# KW2CPU_PCB.net
KiCad netlist of a schematic drawn in EAGLE
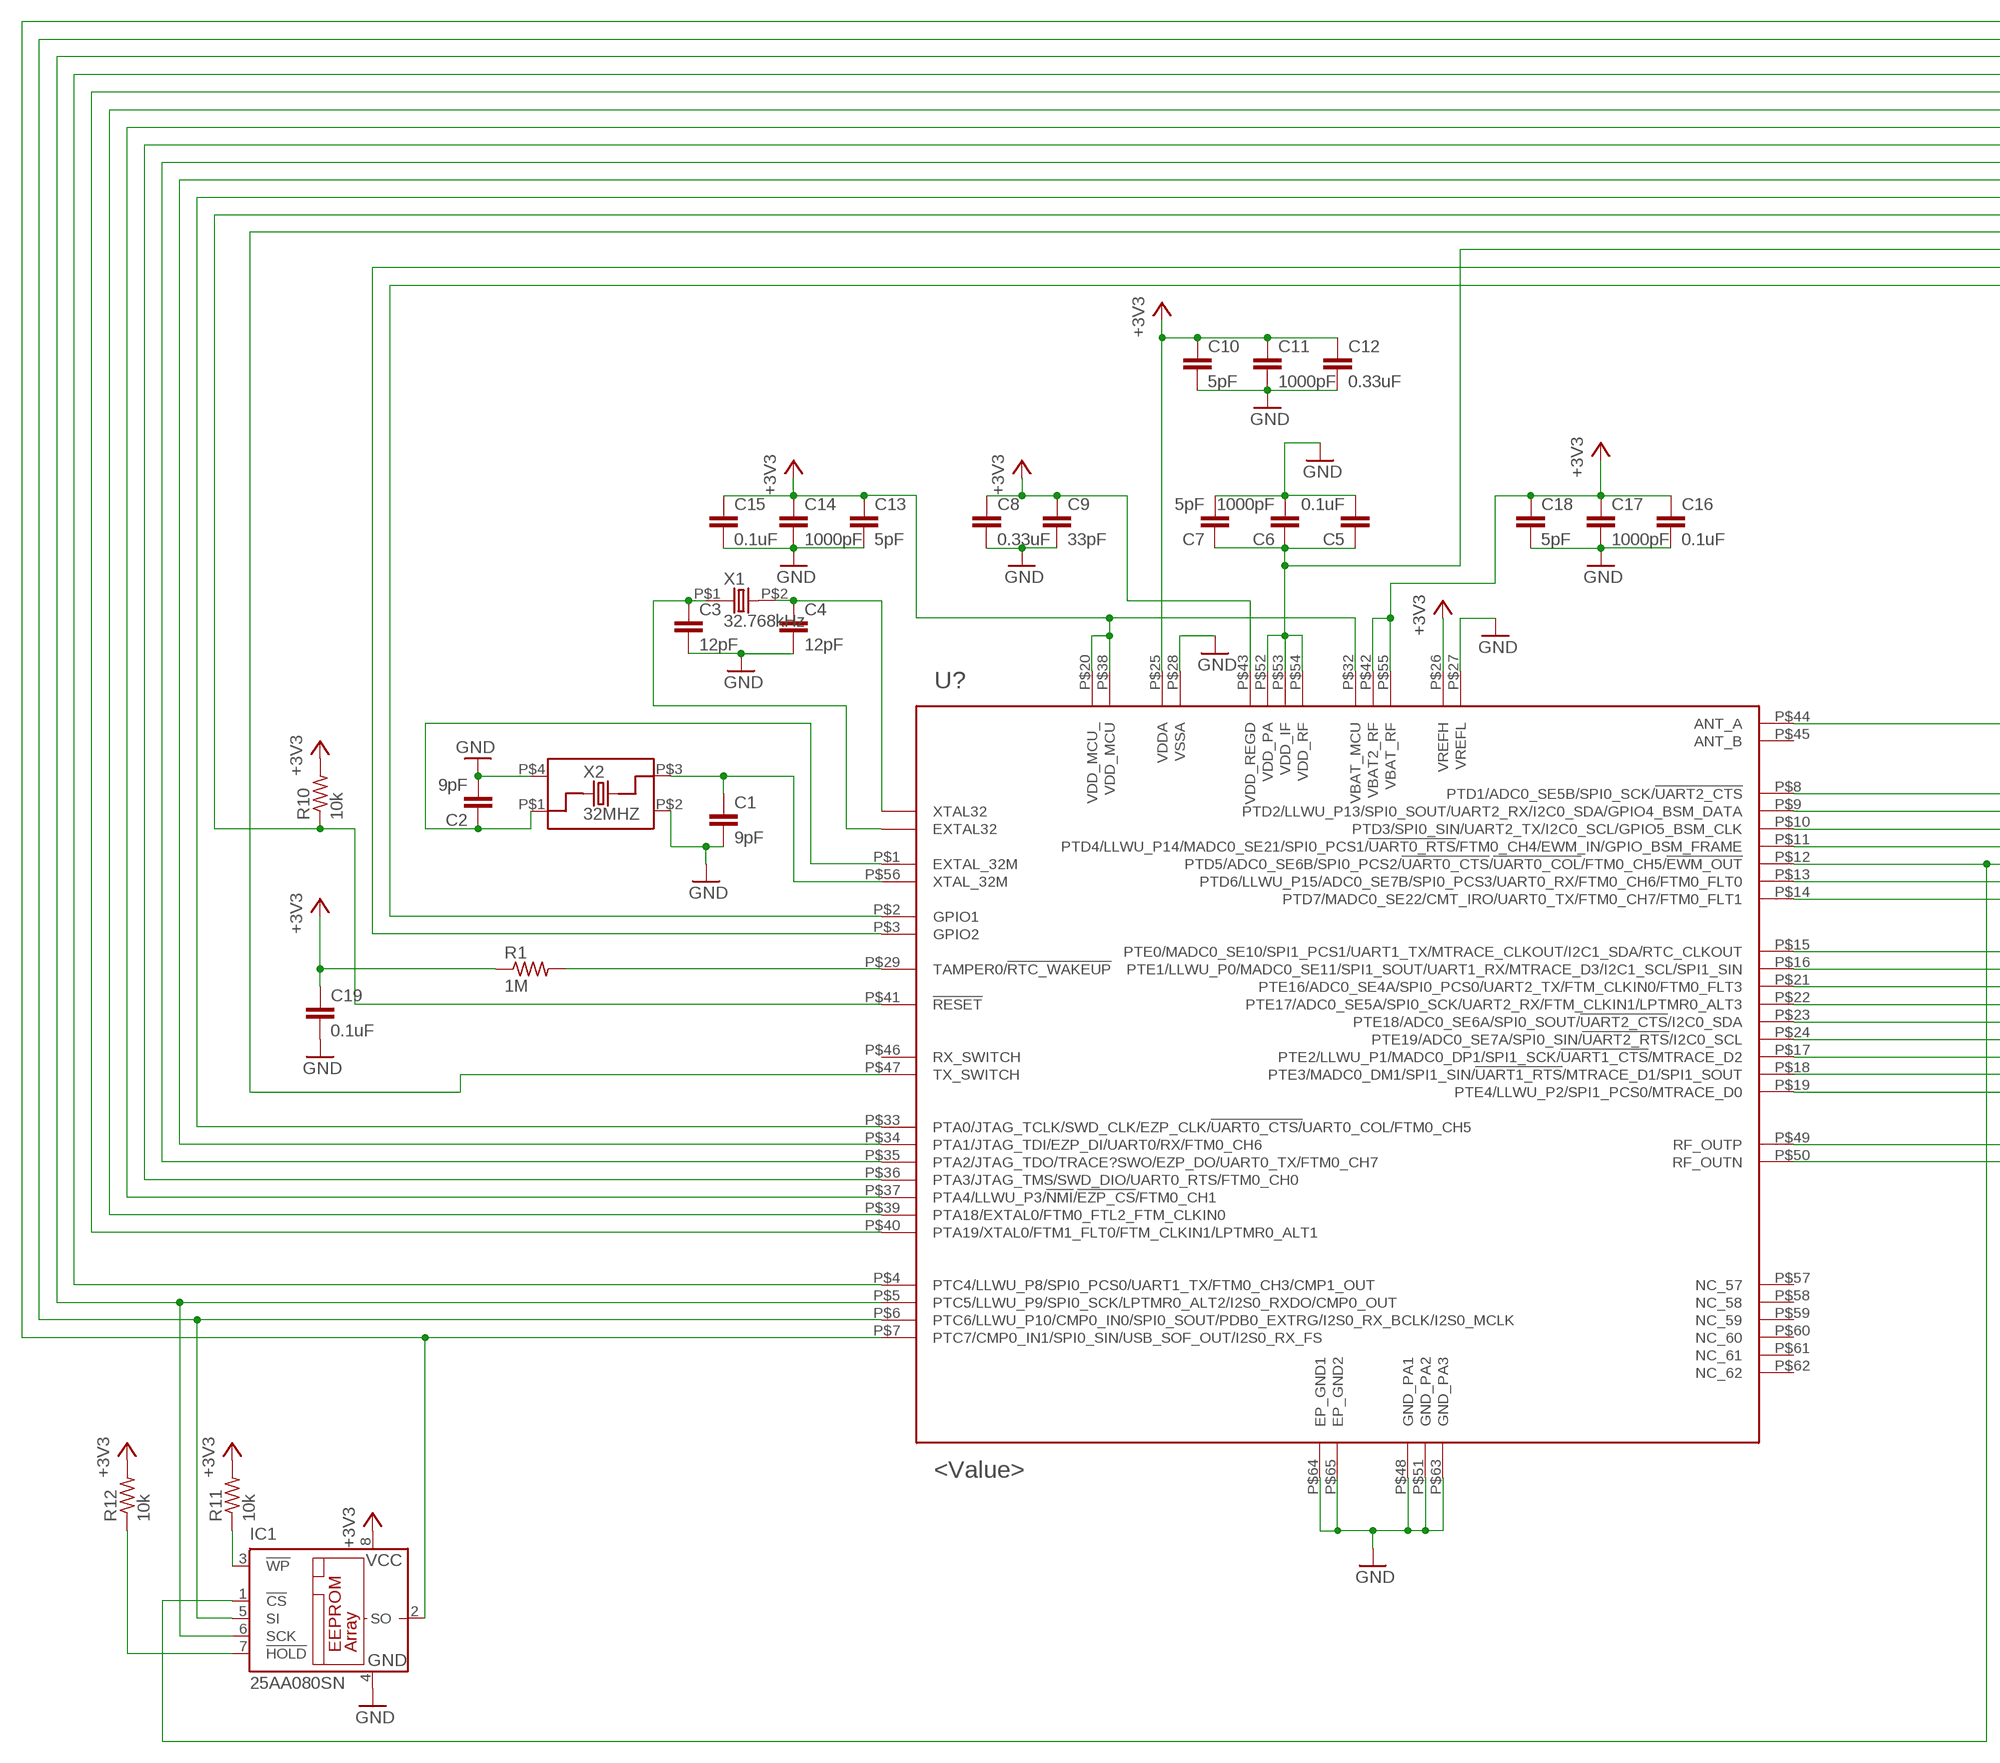
[diagram p0: schematic, sheet 1, part 1 of 2]
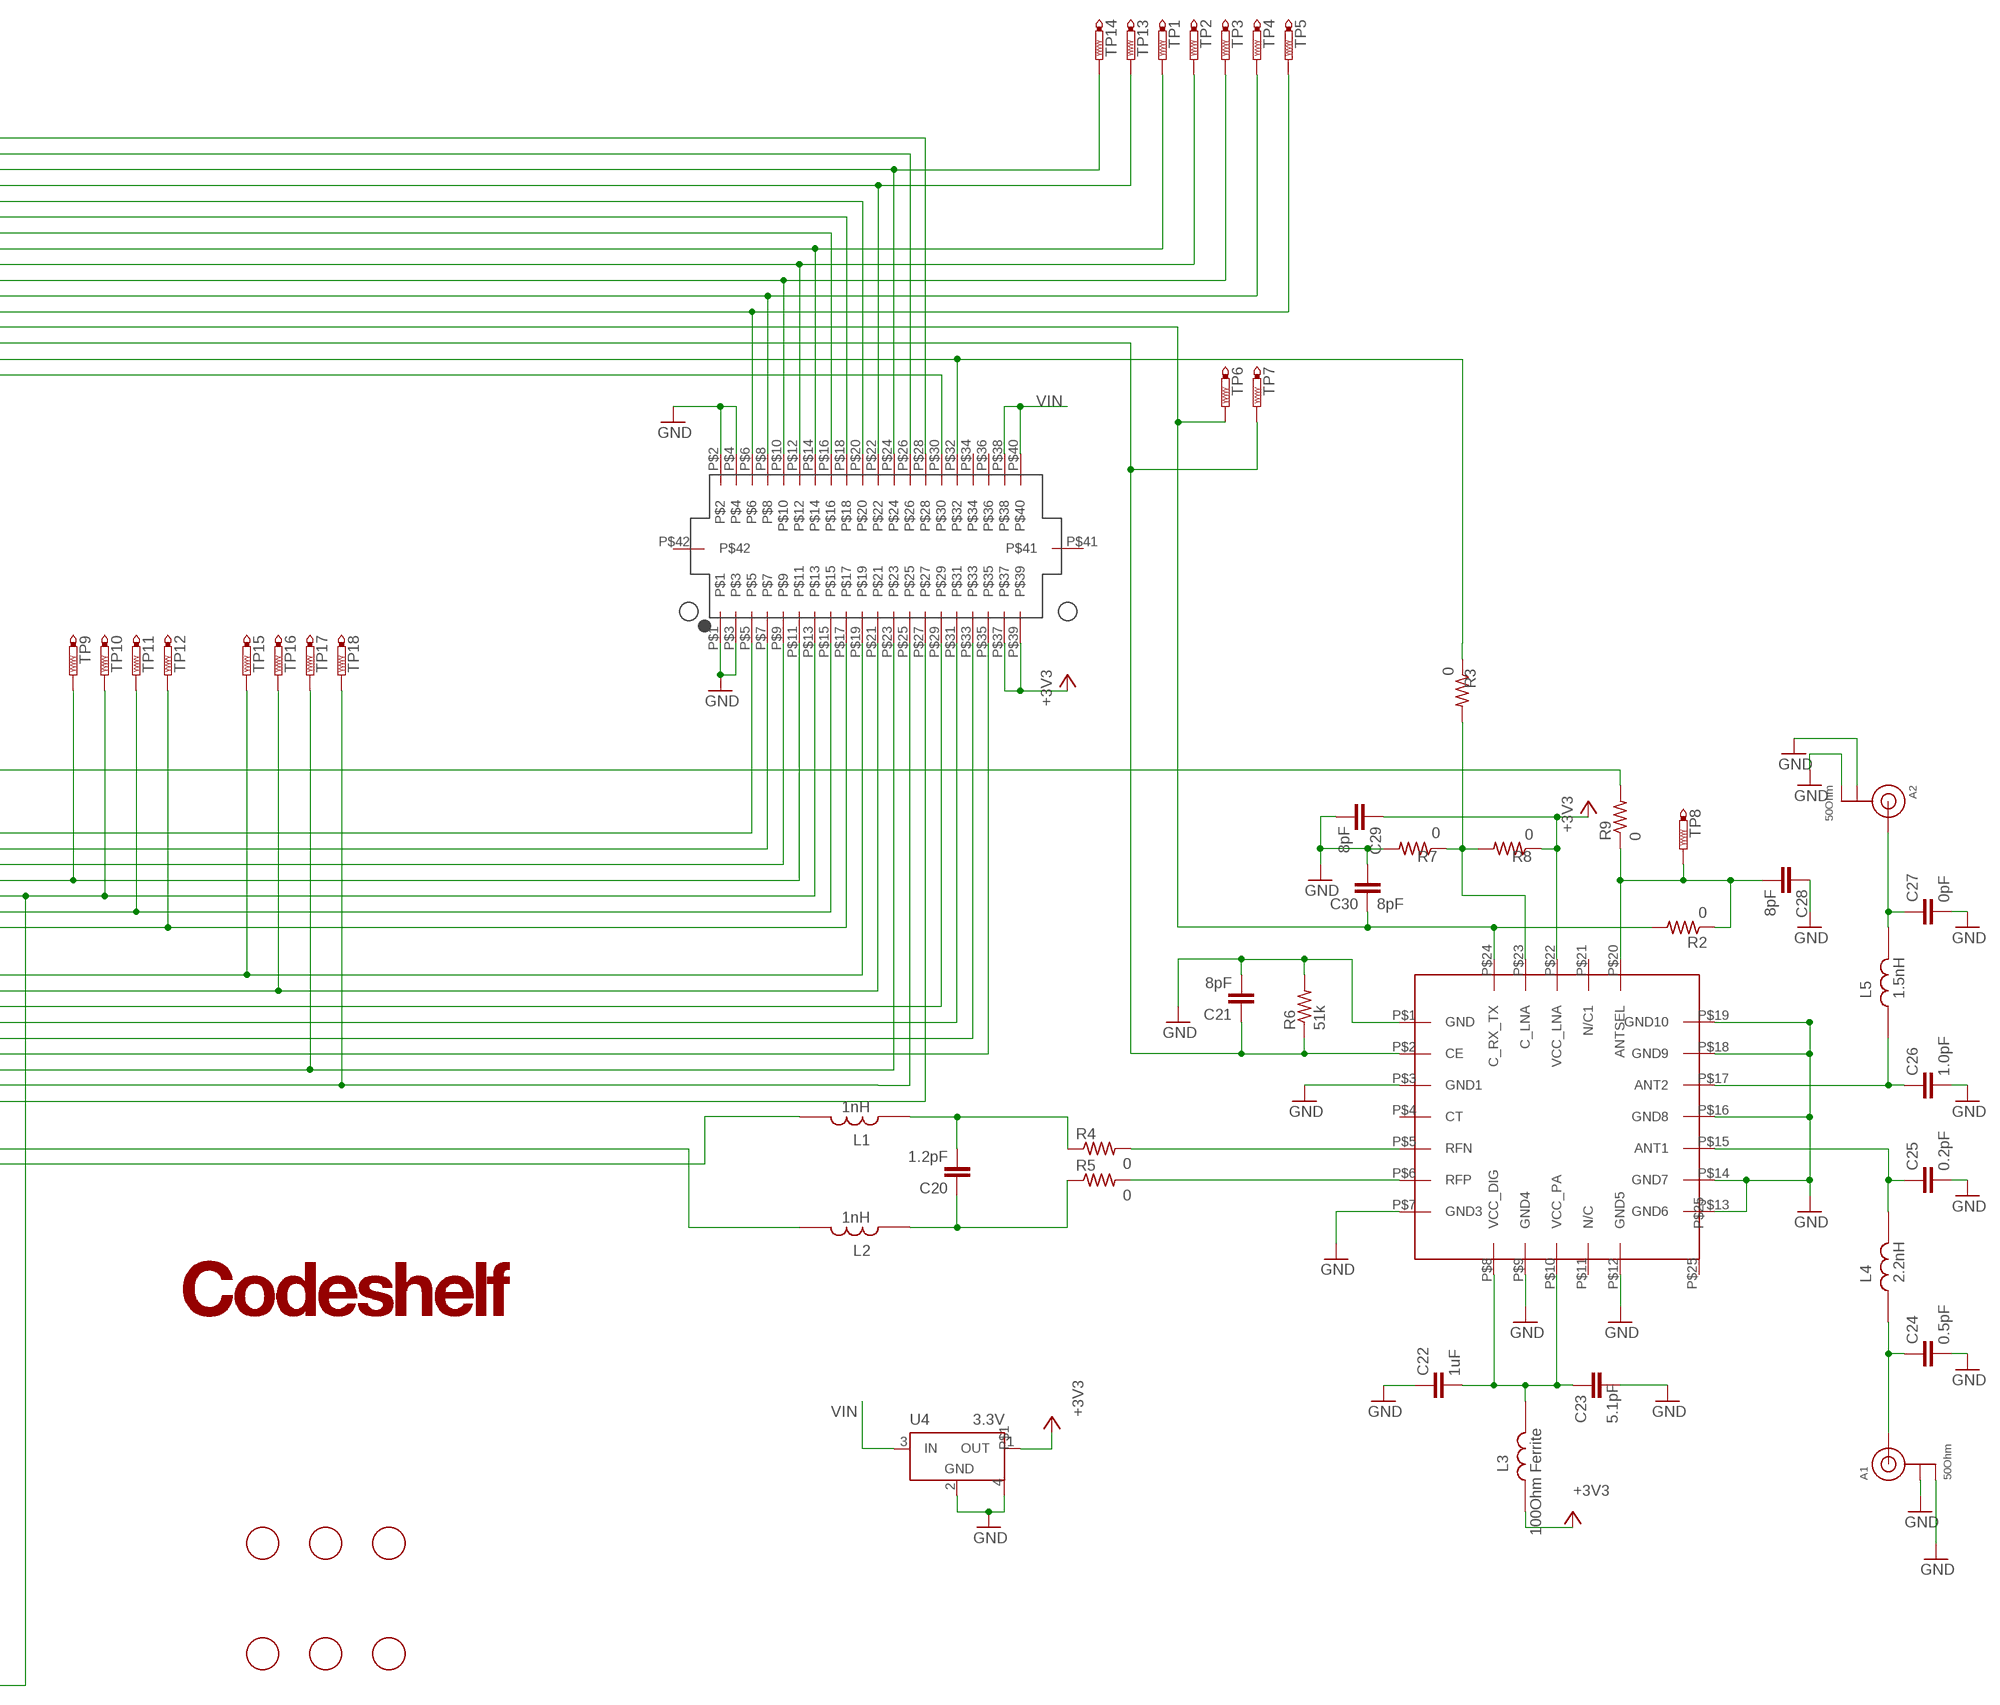
[diagram p1: schematic, sheet 1, part 2 of 2]

(export (version "E")
  (design (tool "Eeschema 10.0.6"))
  (components
    (comp (ref "A1")
      (value "50Ohm")
      (footprint "eagle-import:U.FL")
      (libsource (lib "eagle-import") (part "ANTENNA_U.FL"))
    )
    (comp (ref "A2")
      (value "50Ohm")
      (footprint "eagle-import:U.FL")
      (fields (field (name "MFGN") "Hirose") (field (name "MFGP") "N.FL-R-SMT-1(10)"))
      (libsource (lib "eagle-import") (part "ANTENNA_U.FL"))
    )
    (comp (ref "C1")
      (value "9pF")
      (footprint "eagle-import:C0402")
      (libsource (lib "eagle-import") (part "RF-C0402"))
    )
    (comp (ref "C2")
      (value "9pF")
      (footprint "eagle-import:C0402")
      (libsource (lib "eagle-import") (part "RF-C0402"))
    )
    (comp (ref "C3")
      (value "12pF")
      (footprint "eagle-import:C0402")
      (libsource (lib "eagle-import") (part "RF-C0402"))
    )
    (comp (ref "C4")
      (value "12pF")
      (footprint "eagle-import:C0402")
      (libsource (lib "eagle-import") (part "RF-C0402"))
    )
    (comp (ref "C5")
      (value "0.1uF")
      (footprint "eagle-import:C0402")
      (libsource (lib "eagle-import") (part "RF-C0402"))
    )
    (comp (ref "C6")
      (value "1000pF")
      (footprint "eagle-import:C0402")
      (libsource (lib "eagle-import") (part "RF-C0402"))
    )
    (comp (ref "C7")
      (value "5pF")
      (footprint "eagle-import:C0402")
      (libsource (lib "eagle-import") (part "RF-C0402"))
    )
    (comp (ref "C8")
      (value "0.33uF")
      (footprint "eagle-import:C0402")
      (libsource (lib "eagle-import") (part "RF-C0402"))
    )
    (comp (ref "C9")
      (value "33pF")
      (footprint "eagle-import:C0402")
      (libsource (lib "eagle-import") (part "RF-C0402"))
    )
    (comp (ref "C10")
      (value "5pF")
      (footprint "eagle-import:C0402")
      (libsource (lib "eagle-import") (part "RF-C0402"))
    )
    (comp (ref "C11")
      (value "1000pF")
      (footprint "eagle-import:C0402")
      (libsource (lib "eagle-import") (part "RF-C0402"))
    )
    (comp (ref "C12")
      (value "0.33uF")
      (footprint "eagle-import:C0402")
      (libsource (lib "eagle-import") (part "RF-C0402"))
    )
    (comp (ref "C13")
      (value "5pF")
      (footprint "eagle-import:C0402")
      (libsource (lib "eagle-import") (part "RF-C0402"))
    )
    (comp (ref "C14")
      (value "1000pF")
      (footprint "eagle-import:C0402")
      (libsource (lib "eagle-import") (part "RF-C0402"))
    )
    (comp (ref "C15")
      (value "0.1uF")
      (footprint "eagle-import:C0402")
      (libsource (lib "eagle-import") (part "RF-C0402"))
    )
    (comp (ref "C16")
      (value "0.1uF")
      (footprint "eagle-import:C0402")
      (libsource (lib "eagle-import") (part "RF-C0402"))
    )
    (comp (ref "C17")
      (value "1000pF")
      (footprint "eagle-import:C0402")
      (libsource (lib "eagle-import") (part "RF-C0402"))
    )
    (comp (ref "C18")
      (value "5pF")
      (footprint "eagle-import:C0402")
      (libsource (lib "eagle-import") (part "RF-C0402"))
    )
    (comp (ref "C19")
      (value "0.1uF")
      (footprint "eagle-import:C0402")
      (libsource (lib "eagle-import") (part "RF-C0402"))
    )
    (comp (ref "C20")
      (value "1.2pF")
      (footprint "eagle-import:RF-L0201")
      (libsource (lib "eagle-import") (part "RF-C"))
    )
    (comp (ref "C21")
      (value "8pF")
      (footprint "eagle-import:RFMD0402")
      (libsource (lib "eagle-import") (part "RF-CRFMD"))
    )
    (comp (ref "C22")
      (value "1uF")
      (footprint "eagle-import:RF-L0201")
      (libsource (lib "eagle-import") (part "RF-C"))
    )
    (comp (ref "C23")
      (value "5.1pF")
      (footprint "eagle-import:RF-L0201")
      (libsource (lib "eagle-import") (part "RF-C"))
    )
    (comp (ref "C24")
      (value "0.5pF")
      (footprint "eagle-import:RFMD0402")
      (libsource (lib "eagle-import") (part "RF-CRFMD"))
    )
    (comp (ref "C25")
      (value "0.2pF")
      (footprint "eagle-import:RFMD0402")
      (libsource (lib "eagle-import") (part "RF-CRFMD"))
    )
    (comp (ref "C26")
      (value "1.0pF")
      (footprint "eagle-import:RFMD0402")
      (libsource (lib "eagle-import") (part "RF-CRFMD"))
    )
    (comp (ref "C27")
      (value "0pF")
      (footprint "eagle-import:RFMD0402")
      (libsource (lib "eagle-import") (part "RF-CRFMD"))
    )
    (comp (ref "C28")
      (value "8pF")
      (footprint "eagle-import:RFMD0402")
      (libsource (lib "eagle-import") (part "RF-CRFMD"))
    )
    (comp (ref "C29")
      (value "8pF")
      (footprint "eagle-import:RFMD0402")
      (libsource (lib "eagle-import") (part "RF-CRFMD"))
    )
    (comp (ref "C30")
      (value "8pF")
      (footprint "eagle-import:RFMD0402")
      (libsource (lib "eagle-import") (part "RF-CRFMD"))
    )
    (comp (ref "IC1")
      (value "25AA080SN")
      (footprint "eagle-import:SO-08")
      (fields
        (field (name "MF") "MICROCHIP")
        (field (name "MPN") "25AA080/SN")
        (field (name "MPN_1") "25AA640A")
      )
      (libsource (lib "eagle-import") (part "25SNAA080"))
    )
    (comp (ref "J1")
      (value "DF12_M")
      (footprint "eagle-import:DF12_M")
      (libsource (lib "eagle-import") (part "DF12_M"))
    )
    (comp (ref "L1")
      (value "1nH")
      (footprint "eagle-import:RF-L0201")
      (libsource (lib "eagle-import") (part "RF-L0201"))
    )
    (comp (ref "L2")
      (value "1nH")
      (footprint "eagle-import:RF-L0201")
      (libsource (lib "eagle-import") (part "RF-L0201"))
    )
    (comp (ref "L3")
      (value "100Ohm Ferrite")
      (footprint "eagle-import:RFMD0402")
      (libsource (lib "eagle-import") (part "RF-L"))
    )
    (comp (ref "L4")
      (value "2.2nH")
      (footprint "eagle-import:RFMD0402")
      (libsource (lib "eagle-import") (part "RF-L"))
    )
    (comp (ref "L5")
      (value "1.5nH")
      (footprint "eagle-import:RFMD0402")
      (libsource (lib "eagle-import") (part "RF-L"))
    )
    (comp (ref "R1")
      (value "1M")
      (footprint "eagle-import:RF-R0402")
      (libsource (lib "eagle-import") (part "RF-R0402"))
    )
    (comp (ref "R2")
      (value "0")
      (footprint "eagle-import:RFMD0402")
      (libsource (lib "eagle-import") (part "RF-RRFMD"))
    )
    (comp (ref "R3")
      (value "0")
      (footprint "eagle-import:RFMD0402")
      (libsource (lib "eagle-import") (part "RF-RRFMD"))
    )
    (comp (ref "R4")
      (value "0")
      (footprint "eagle-import:RF-L0201")
      (libsource (lib "eagle-import") (part "RF-R"))
    )
    (comp (ref "R5")
      (value "0")
      (footprint "eagle-import:RF-L0201")
      (libsource (lib "eagle-import") (part "RF-R"))
    )
    (comp (ref "R6")
      (value "51k")
      (footprint "eagle-import:RFMD0402")
      (libsource (lib "eagle-import") (part "RF-RRFMD"))
    )
    (comp (ref "R7")
      (value "0")
      (footprint "eagle-import:RFMD0402")
      (libsource (lib "eagle-import") (part "RF-RRFMD"))
    )
    (comp (ref "R8")
      (value "0")
      (footprint "eagle-import:RFMD0402")
      (libsource (lib "eagle-import") (part "RF-RRFMD"))
    )
    (comp (ref "R9")
      (value "0")
      (footprint "eagle-import:RFMD0402")
      (libsource (lib "eagle-import") (part "RF-RRFMD"))
    )
    (comp (ref "R10")
      (value "10k")
      (footprint "eagle-import:RF-R0402")
      (libsource (lib "eagle-import") (part "RF-R0402"))
    )
    (comp (ref "R11")
      (value "10k")
      (footprint "eagle-import:RF-R0402")
      (libsource (lib "eagle-import") (part "RF-R0402"))
    )
    (comp (ref "R12")
      (value "10k")
      (footprint "eagle-import:RF-R0402")
      (libsource (lib "eagle-import") (part "RF-R0402"))
    )
    (comp (ref "TP1")
      (value "PTR1TP15R")
      (footprint "eagle-import:TP15R")
      (libsource (lib "eagle-import") (part "PTR1TP15R"))
    )
    (comp (ref "TP2")
      (value "PTR1TP15R")
      (footprint "eagle-import:TP15R")
      (libsource (lib "eagle-import") (part "PTR1TP15R"))
    )
    (comp (ref "TP3")
      (value "PTR1TP15R")
      (footprint "eagle-import:TP15R")
      (libsource (lib "eagle-import") (part "PTR1TP15R"))
    )
    (comp (ref "TP4")
      (value "PTR1TP15R")
      (footprint "eagle-import:TP15R")
      (libsource (lib "eagle-import") (part "PTR1TP15R"))
    )
    (comp (ref "TP5")
      (value "PTR1TP15R")
      (footprint "eagle-import:TP15R")
      (libsource (lib "eagle-import") (part "PTR1TP15R"))
    )
    (comp (ref "TP6")
      (value "PTR1TP15R")
      (footprint "eagle-import:TP15R")
      (libsource (lib "eagle-import") (part "PTR1TP15R"))
    )
    (comp (ref "TP7")
      (value "PTR1TP15R")
      (footprint "eagle-import:TP15R")
      (libsource (lib "eagle-import") (part "PTR1TP15R"))
    )
    (comp (ref "TP8")
      (value "PTR1TP15R")
      (footprint "eagle-import:TP15R")
      (libsource (lib "eagle-import") (part "PTR1TP15R"))
    )
    (comp (ref "TP9")
      (value "PTR1TP15R")
      (footprint "eagle-import:TP15R")
      (libsource (lib "eagle-import") (part "PTR1TP15R"))
    )
    (comp (ref "TP10")
      (value "PTR1TP15R")
      (footprint "eagle-import:TP15R")
      (libsource (lib "eagle-import") (part "PTR1TP15R"))
    )
    (comp (ref "TP11")
      (value "PTR1TP15R")
      (footprint "eagle-import:TP15R")
      (libsource (lib "eagle-import") (part "PTR1TP15R"))
    )
    (comp (ref "TP12")
      (value "PTR1TP15R")
      (footprint "eagle-import:TP15R")
      (libsource (lib "eagle-import") (part "PTR1TP15R"))
    )
    (comp (ref "TP13")
      (value "PTR1TP15R")
      (footprint "eagle-import:TP15R")
      (libsource (lib "eagle-import") (part "PTR1TP15R"))
    )
    (comp (ref "TP14")
      (value "PTR1TP15R")
      (footprint "eagle-import:TP15R")
      (libsource (lib "eagle-import") (part "PTR1TP15R"))
    )
    (comp (ref "TP15")
      (value "PTR1TP15R")
      (footprint "eagle-import:TP15R")
      (libsource (lib "eagle-import") (part "PTR1TP15R"))
    )
    (comp (ref "TP16")
      (value "PTR1TP15R")
      (footprint "eagle-import:TP15R")
      (libsource (lib "eagle-import") (part "PTR1TP15R"))
    )
    (comp (ref "TP17")
      (value "PTR1TP15R")
      (footprint "eagle-import:TP15R")
      (libsource (lib "eagle-import") (part "PTR1TP15R"))
    )
    (comp (ref "TP18")
      (value "PTR1TP15R")
      (footprint "eagle-import:TP15R")
      (libsource (lib "eagle-import") (part "PTR1TP15R"))
    )
    (comp (ref "U$1")
      (value "CODESHELF-LOGOSMALL")
      (footprint "eagle-import:CODESHELF-LOGO-SMALL")
      (libsource (lib "eagle-import") (part "CODESHELF-LOGOSMALL"))
    )
    (comp (ref "U$2")
      (value "FIDUCIAL")
      (footprint "eagle-import:FIDUCIAL_1MM")
      (libsource (lib "eagle-import") (part "FIDUCIAL"))
    )
    (comp (ref "U$3")
      (value "FIDUCIAL")
      (footprint "eagle-import:FIDUCIAL_1MM")
      (libsource (lib "eagle-import") (part "FIDUCIAL"))
    )
    (comp (ref "U$4")
      (value "FIDUCIAL")
      (footprint "eagle-import:FIDUCIAL_1MM")
      (libsource (lib "eagle-import") (part "FIDUCIAL"))
    )
    (comp (ref "U$5")
      (value "FIDUCIAL")
      (footprint "eagle-import:FIDUCIAL_1MM")
      (libsource (lib "eagle-import") (part "FIDUCIAL"))
    )
    (comp (ref "U$6")
      (value "FIDUCIAL")
      (footprint "eagle-import:FIDUCIAL_1MM")
      (libsource (lib "eagle-import") (part "FIDUCIAL"))
    )
    (comp (ref "U$7")
      (value "FIDUCIAL")
      (footprint "eagle-import:FIDUCIAL_1MM")
      (libsource (lib "eagle-import") (part "FIDUCIAL"))
    )
    (comp (ref "U1")
      (value "MKW21D")
      (footprint "eagle-import:LGA63")
      (libsource (lib "eagle-import") (part "MKW21D"))
    )
    (comp (ref "U3")
      (value "RF6555")
      (footprint "eagle-import:RF6555")
      (libsource (lib "eagle-import") (part "RF6555"))
    )
    (comp (ref "U4")
      (value "3.3V")
      (footprint "eagle-import:SOT223")
      (fields (field (name "MPN") "MCP1804T-3302I"))
      (libsource (lib "eagle-import") (part "MCP1804T-3302I"))
    )
    (comp (ref "X1")
      (value "32.768kHz")
      (footprint "eagle-import:32KHZSMD")
      (libsource (lib "eagle-import") (part "32KHZ"))
    )
    (comp (ref "X2")
      (value "32MHZ")
      (footprint "eagle-import:32MHZSMD")
      (libsource (lib "eagle-import") (part "32MHZ"))
    )
  )
  (nets
    (net (code "1") (name "+3V3") (class "Default")
      (node (ref "C10") (pin "1") (pinfunction "1_1") (pintype "passive"))
      (node (ref "C11") (pin "1") (pinfunction "1_1") (pintype "passive"))
      (node (ref "C12") (pin "1") (pinfunction "1_1") (pintype "passive"))
      (node (ref "C13") (pin "1") (pinfunction "1_1") (pintype "passive"))
      (node (ref "C14") (pin "1") (pinfunction "1_1") (pintype "passive"))
      (node (ref "C15") (pin "1") (pinfunction "1_1") (pintype "passive"))
      (node (ref "C16") (pin "1") (pinfunction "1_1") (pintype "passive"))
      (node (ref "C17") (pin "1") (pinfunction "1_1") (pintype "passive"))
      (node (ref "C18") (pin "1") (pinfunction "1_1") (pintype "passive"))
      (node (ref "C19") (pin "1") (pinfunction "1_1") (pintype "passive"))
      (node (ref "C29") (pin "P$1") (pinfunction "1_P$1") (pintype "passive"))
      (node (ref "C8") (pin "1") (pinfunction "1_1") (pintype "passive"))
      (node (ref "C9") (pin "1") (pinfunction "1_1") (pintype "passive"))
      (node (ref "IC1") (pin "8") (pinfunction "VCC_8") (pintype "power_in"))
      (node (ref "J1") (pin "P$37") (pinfunction "P$37_P$37") (pintype "bidirectional"))
      (node (ref "J1") (pin "P$39") (pinfunction "P$39_P$39") (pintype "bidirectional"))
      (node (ref "L3") (pin "P$2") (pinfunction "2_P$2") (pintype "bidirectional"))
      (node (ref "R1") (pin "1") (pinfunction "1_1") (pintype "passive"))
      (node (ref "R10") (pin "2") (pinfunction "2_2") (pintype "passive"))
      (node (ref "R11") (pin "2") (pinfunction "2_2") (pintype "passive"))
      (node (ref "R12") (pin "2") (pinfunction "2_2") (pintype "passive"))
      (node (ref "R8") (pin "P$1") (pinfunction "1_P$1") (pintype "passive"))
      (node (ref "U1") (pin "P$20") (pinfunction "VDD_MCU__P$20") (pintype "bidirectional"))
      (node (ref "U1") (pin "P$25") (pinfunction "VDDA_P$25") (pintype "bidirectional"))
      (node (ref "U1") (pin "P$26") (pinfunction "VREFH_P$26") (pintype "bidirectional"))
      (node (ref "U1") (pin "P$32") (pinfunction "VBAT_MCU_P$32") (pintype "bidirectional"))
      (node (ref "U1") (pin "P$38") (pinfunction "VDD_MCU_P$38") (pintype "bidirectional"))
      (node (ref "U1") (pin "P$42") (pinfunction "VBAT2_RF_P$42") (pintype "bidirectional"))
      (node (ref "U1") (pin "P$43") (pinfunction "VDD_REGD_P$43") (pintype "bidirectional"))
      (node (ref "U1") (pin "P$55") (pinfunction "VBAT_RF_P$55") (pintype "bidirectional"))
      (node (ref "U3") (pin "P$22") (pinfunction "VCC_LNA_P$22") (pintype "bidirectional"))
      (node (ref "U4") (pin "1") (pinfunction "OUT_1") (pintype "output"))
    )
    (net (code "2") (name "/VIN") (class "Default")
      (node (ref "J1") (pin "P$38") (pinfunction "P$38_P$38") (pintype "bidirectional"))
      (node (ref "J1") (pin "P$40") (pinfunction "P$40_P$40") (pintype "bidirectional"))
      (node (ref "U4") (pin "3") (pinfunction "IN_3") (pintype "input"))
    )
    (net (code "3") (name "GND") (class "Default")
      (node (ref "A1") (pin "1") (pinfunction "GND_1") (pintype "passive"))
      (node (ref "A1") (pin "2") (pinfunction "GND_2") (pintype "passive"))
      (node (ref "A2") (pin "1") (pinfunction "GND_1") (pintype "passive"))
      (node (ref "A2") (pin "2") (pinfunction "GND_2") (pintype "passive"))
      (node (ref "C1") (pin "2") (pinfunction "2_2") (pintype "passive"))
      (node (ref "C10") (pin "2") (pinfunction "2_2") (pintype "passive"))
      (node (ref "C11") (pin "2") (pinfunction "2_2") (pintype "passive"))
      (node (ref "C12") (pin "2") (pinfunction "2_2") (pintype "passive"))
      (node (ref "C13") (pin "2") (pinfunction "2_2") (pintype "passive"))
      (node (ref "C14") (pin "2") (pinfunction "2_2") (pintype "passive"))
      (node (ref "C15") (pin "2") (pinfunction "2_2") (pintype "passive"))
      (node (ref "C16") (pin "2") (pinfunction "2_2") (pintype "passive"))
      (node (ref "C17") (pin "2") (pinfunction "2_2") (pintype "passive"))
      (node (ref "C18") (pin "2") (pinfunction "2_2") (pintype "passive"))
      (node (ref "C19") (pin "2") (pinfunction "2_2") (pintype "passive"))
      (node (ref "C2") (pin "2") (pinfunction "2_2") (pintype "passive"))
      (node (ref "C21") (pin "P$2") (pinfunction "2_P$2") (pintype "passive"))
      (node (ref "C22") (pin "P$1") (pinfunction "1_P$1") (pintype "passive"))
      (node (ref "C23") (pin "P$2") (pinfunction "2_P$2") (pintype "passive"))
      (node (ref "C24") (pin "P$2") (pinfunction "2_P$2") (pintype "passive"))
      (node (ref "C25") (pin "P$2") (pinfunction "2_P$2") (pintype "passive"))
      (node (ref "C26") (pin "P$2") (pinfunction "2_P$2") (pintype "passive"))
      (node (ref "C27") (pin "P$2") (pinfunction "2_P$2") (pintype "passive"))
      (node (ref "C28") (pin "P$1") (pinfunction "1_P$1") (pintype "passive"))
      (node (ref "C29") (pin "P$2") (pinfunction "2_P$2") (pintype "passive"))
      (node (ref "C3") (pin "2") (pinfunction "2_2") (pintype "passive"))
      (node (ref "C30") (pin "P$1") (pinfunction "1_P$1") (pintype "passive"))
      (node (ref "C4") (pin "2") (pinfunction "2_2") (pintype "passive"))
      (node (ref "C5") (pin "2") (pinfunction "2_2") (pintype "passive"))
      (node (ref "C6") (pin "2") (pinfunction "2_2") (pintype "passive"))
      (node (ref "C7") (pin "2") (pinfunction "2_2") (pintype "passive"))
      (node (ref "C8") (pin "2") (pinfunction "2_2") (pintype "passive"))
      (node (ref "C9") (pin "2") (pinfunction "2_2") (pintype "passive"))
      (node (ref "IC1") (pin "4") (pinfunction "GND_4") (pintype "power_in"))
      (node (ref "J1") (pin "P$1") (pinfunction "P$1_P$1") (pintype "bidirectional"))
      (node (ref "J1") (pin "P$2") (pinfunction "P$2_P$2") (pintype "bidirectional"))
      (node (ref "J1") (pin "P$3") (pinfunction "P$3_P$3") (pintype "bidirectional"))
      (node (ref "J1") (pin "P$4") (pinfunction "P$4_P$4") (pintype "bidirectional"))
      (node (ref "R6") (pin "P$2") (pinfunction "2_P$2") (pintype "passive"))
      (node (ref "R7") (pin "P$2") (pinfunction "2_P$2") (pintype "passive"))
      (node (ref "U1") (pin "P$27") (pinfunction "VREFL_P$27") (pintype "bidirectional"))
      (node (ref "U1") (pin "P$28") (pinfunction "VSSA_P$28") (pintype "bidirectional"))
      (node (ref "U1") (pin "P$48") (pinfunction "GND_PA1_P$48") (pintype "bidirectional"))
      (node (ref "U1") (pin "P$51") (pinfunction "GND_PA2_P$51") (pintype "bidirectional"))
      (node (ref "U1") (pin "P$63") (pinfunction "GND_PA3_P$63") (pintype "bidirectional"))
      (node (ref "U1") (pin "P$64") (pinfunction "EP_GND1_P$64") (pintype "bidirectional"))
      (node (ref "U1") (pin "P$65") (pinfunction "EP_GND2_P$65") (pintype "bidirectional"))
      (node (ref "U3") (pin "P$1") (pinfunction "GND_P$1") (pintype "bidirectional"))
      (node (ref "U3") (pin "P$12") (pinfunction "GND5_P$12") (pintype "bidirectional"))
      (node (ref "U3") (pin "P$13") (pinfunction "GND6_P$13") (pintype "bidirectional"))
      (node (ref "U3") (pin "P$14") (pinfunction "GND7_P$14") (pintype "bidirectional"))
      (node (ref "U3") (pin "P$16") (pinfunction "GND8_P$16") (pintype "bidirectional"))
      (node (ref "U3") (pin "P$18") (pinfunction "GND9_P$18") (pintype "bidirectional"))
      (node (ref "U3") (pin "P$19") (pinfunction "GND10_P$19") (pintype "bidirectional"))
      (node (ref "U3") (pin "P$3") (pinfunction "GND1_P$3") (pintype "bidirectional"))
      (node (ref "U3") (pin "P$7") (pinfunction "GND3_P$7") (pintype "bidirectional"))
      (node (ref "U3") (pin "P$9") (pinfunction "GND4_P$9") (pintype "bidirectional"))
      (node (ref "U4") (pin "2") (pinfunction "GND_2") (pintype "power_in"))
      (node (ref "U4") (pin "4") (pinfunction "P$1_4") (pintype "bidirectional"))
      (node (ref "X2") (pin "P$2") (pinfunction "P$2_P$2") (pintype "power_in"))
      (node (ref "X2") (pin "P$4") (pinfunction "P$4_P$4") (pintype "bidirectional"))
    )
    (net (code "4") (name "Net-(A1-SIGNAL)") (class "Default")
      (node (ref "A1") (pin "3") (pinfunction "SIGNAL_3") (pintype "passive"))
      (node (ref "C24") (pin "P$1") (pinfunction "1_P$1") (pintype "passive"))
      (node (ref "L4") (pin "P$2") (pinfunction "2_P$2") (pintype "bidirectional"))
    )
    (net (code "5") (name "Net-(A2-SIGNAL)") (class "Default")
      (node (ref "A2") (pin "3") (pinfunction "SIGNAL_3") (pintype "passive"))
      (node (ref "C27") (pin "P$1") (pinfunction "1_P$1") (pintype "passive"))
      (node (ref "L5") (pin "P$1") (pinfunction "1_P$1") (pintype "bidirectional"))
    )
    (net (code "6") (name "Net-(C20-1)") (class "Default")
      (node (ref "C20") (pin "P$1") (pinfunction "1_P$1") (pintype "passive"))
      (node (ref "L2") (pin "P$2") (pinfunction "2_P$2") (pintype "bidirectional"))
      (node (ref "R5") (pin "P$1") (pinfunction "1_P$1") (pintype "passive"))
    )
    (net (code "7") (name "Net-(C20-2)") (class "Default")
      (node (ref "C20") (pin "P$2") (pinfunction "2_P$2") (pintype "passive"))
      (node (ref "L1") (pin "P$2") (pinfunction "2_P$2") (pintype "bidirectional"))
      (node (ref "R4") (pin "P$1") (pinfunction "1_P$1") (pintype "passive"))
    )
    (net (code "8") (name "Net-(C21-1)") (class "Default")
      (node (ref "C21") (pin "P$1") (pinfunction "1_P$1") (pintype "passive"))
      (node (ref "C5") (pin "1") (pinfunction "1_1") (pintype "passive"))
      (node (ref "C6") (pin "1") (pinfunction "1_1") (pintype "passive"))
      (node (ref "C7") (pin "1") (pinfunction "1_1") (pintype "passive"))
      (node (ref "R6") (pin "P$1") (pinfunction "1_P$1") (pintype "passive"))
      (node (ref "TP7") (pin "TP") (pinfunction "TP_TP") (pintype "input"))
      (node (ref "U1") (pin "P$52") (pinfunction "VDD_PA_P$52") (pintype "bidirectional"))
      (node (ref "U1") (pin "P$53") (pinfunction "VDD_IF_P$53") (pintype "bidirectional"))
      (node (ref "U1") (pin "P$54") (pinfunction "VDD_RF_P$54") (pintype "bidirectional"))
      (node (ref "U3") (pin "P$2") (pinfunction "CE_P$2") (pintype "bidirectional"))
    )
    (net (code "9") (name "Net-(C22-2)") (class "Default")
      (node (ref "C22") (pin "P$2") (pinfunction "2_P$2") (pintype "passive"))
      (node (ref "C23") (pin "P$1") (pinfunction "1_P$1") (pintype "passive"))
      (node (ref "L3") (pin "P$1") (pinfunction "1_P$1") (pintype "bidirectional"))
      (node (ref "U3") (pin "P$10") (pinfunction "VCC_PA_P$10") (pintype "bidirectional"))
      (node (ref "U3") (pin "P$8") (pinfunction "VCC_DIG_P$8") (pintype "bidirectional"))
    )
    (net (code "10") (name "Net-(C25-1)") (class "Default")
      (node (ref "C25") (pin "P$1") (pinfunction "1_P$1") (pintype "passive"))
      (node (ref "L4") (pin "P$1") (pinfunction "1_P$1") (pintype "bidirectional"))
      (node (ref "U3") (pin "P$15") (pinfunction "ANT1_P$15") (pintype "bidirectional"))
    )
    (net (code "11") (name "Net-(C26-1)") (class "Default")
      (node (ref "C26") (pin "P$1") (pinfunction "1_P$1") (pintype "passive"))
      (node (ref "L5") (pin "P$2") (pinfunction "2_P$2") (pintype "bidirectional"))
      (node (ref "U3") (pin "P$17") (pinfunction "ANT2_P$17") (pintype "bidirectional"))
    )
    (net (code "12") (name "Net-(C28-2)") (class "Default")
      (node (ref "C28") (pin "P$2") (pinfunction "2_P$2") (pintype "passive"))
      (node (ref "R2") (pin "P$1") (pinfunction "1_P$1") (pintype "passive"))
      (node (ref "R9") (pin "P$1") (pinfunction "1_P$1") (pintype "passive"))
      (node (ref "TP8") (pin "TP") (pinfunction "TP_TP") (pintype "input"))
      (node (ref "U3") (pin "P$20") (pinfunction "ANTSEL_P$20") (pintype "bidirectional"))
    )
    (net (code "13") (name "Net-(C30-2)") (class "Default")
      (node (ref "C30") (pin "P$2") (pinfunction "2_P$2") (pintype "passive"))
      (node (ref "R2") (pin "P$2") (pinfunction "2_P$2") (pintype "passive"))
      (node (ref "TP6") (pin "TP") (pinfunction "TP_TP") (pintype "input"))
      (node (ref "U1") (pin "P$47") (pinfunction "TX_SWITCH_P$47") (pintype "bidirectional"))
      (node (ref "U3") (pin "P$24") (pinfunction "C_RX_TX_P$24") (pintype "bidirectional"))
    )
    (net (code "14") (name "Net-(IC1-SCK)") (class "Default")
      (node (ref "IC1") (pin "6") (pinfunction "SCK_6") (pintype "input"))
      (node (ref "J1") (pin "P$24") (pinfunction "P$24_P$24") (pintype "bidirectional"))
      (node (ref "TP14") (pin "TP") (pinfunction "TP_TP") (pintype "input"))
      (node (ref "U1") (pin "P$5") (pinfunction "PTC5/LLWU_P9/SPI0_SCK/LPTMR0_ALT2/I2S0_RXDO/CMP0_OUT_P$5") (pintype "bidirectional"))
    )
    (net (code "15") (name "Net-(IC1-SI)") (class "Default")
      (node (ref "IC1") (pin "5") (pinfunction "SI_5") (pintype "input"))
      (node (ref "J1") (pin "P$26") (pinfunction "P$26_P$26") (pintype "bidirectional"))
      (node (ref "U1") (pin "P$6") (pinfunction "PTC6/LLWU_P10/CMP0_IN0/SPI0_SOUT/PDB0_EXTRG/I2S0_RX_BCLK/I2S0_MCLK_P$6") (pintype "bidirectional"))
    )
    (net (code "16") (name "Net-(IC1-SO)") (class "Default")
      (node (ref "IC1") (pin "2") (pinfunction "SO_2") (pintype "bidirectional"))
      (node (ref "J1") (pin "P$28") (pinfunction "P$28_P$28") (pintype "bidirectional"))
      (node (ref "U1") (pin "P$7") (pinfunction "PTC7/CMP0_IN1/SPI0_SIN/USB_SOF_OUT/I2S0_RX_FS_P$7") (pintype "bidirectional"))
    )
    (net (code "17") (name "Net-(IC1-~{CS})") (class "Default")
      (node (ref "IC1") (pin "1") (pinfunction "~{CS}_1") (pintype "input"))
      (node (ref "J1") (pin "P$13") (pinfunction "P$13_P$13") (pintype "bidirectional"))
      (node (ref "TP10") (pin "TP") (pinfunction "TP_TP") (pintype "input"))
      (node (ref "U1") (pin "P$12") (pinfunction "PTD5/ADC0_SE6B/SPI0_PCS2/~{UART0_CTS}/~{UART0_COL}/FTM0_CH5/~{EWM_OUT}_P$12") (pintype "bidirectional"))
    )
    (net (code "18") (name "Net-(IC1-~{HOLD})") (class "Default")
      (node (ref "IC1") (pin "7") (pinfunction "~{HOLD}_7") (pintype "input"))
      (node (ref "R12") (pin "1") (pinfunction "1_1") (pintype "passive"))
    )
    (net (code "19") (name "Net-(IC1-~{WP})") (class "Default")
      (node (ref "IC1") (pin "3") (pinfunction "~{WP}_3") (pintype "input"))
      (node (ref "R11") (pin "1") (pinfunction "1_1") (pintype "passive"))
    )
    (net (code "20") (name "Net-(L1-1)") (class "Default")
      (node (ref "L1") (pin "P$1") (pinfunction "1_P$1") (pintype "bidirectional"))
      (node (ref "U1") (pin "P$50") (pinfunction "RF_OUTN_P$50") (pintype "bidirectional"))
    )
    (net (code "21") (name "Net-(L2-1)") (class "Default")
      (node (ref "L2") (pin "P$1") (pinfunction "1_P$1") (pintype "bidirectional"))
      (node (ref "U1") (pin "P$49") (pinfunction "RF_OUTP_P$49") (pintype "bidirectional"))
    )
    (net (code "22") (name "Net-(R3-1)") (class "Default")
      (node (ref "J1") (pin "P$32") (pinfunction "P$32_P$32") (pintype "bidirectional"))
      (node (ref "R3") (pin "P$1") (pinfunction "1_P$1") (pintype "passive"))
      (node (ref "U1") (pin "P$3") (pinfunction "GPIO2_P$3") (pintype "bidirectional"))
    )
    (net (code "23") (name "Net-(R3-2)") (class "Default")
      (node (ref "R3") (pin "P$2") (pinfunction "2_P$2") (pintype "passive"))
      (node (ref "R7") (pin "P$1") (pinfunction "1_P$1") (pintype "passive"))
      (node (ref "R8") (pin "P$2") (pinfunction "2_P$2") (pintype "passive"))
      (node (ref "U3") (pin "P$23") (pinfunction "C_LNA_P$23") (pintype "bidirectional"))
    )
    (net (code "24") (name "Net-(R4-2)") (class "Default")
      (node (ref "R4") (pin "P$2") (pinfunction "2_P$2") (pintype "passive"))
      (node (ref "U3") (pin "P$5") (pinfunction "RFN_P$5") (pintype "bidirectional"))
    )
    (net (code "25") (name "Net-(R5-2)") (class "Default")
      (node (ref "R5") (pin "P$2") (pinfunction "2_P$2") (pintype "passive"))
      (node (ref "U3") (pin "P$6") (pinfunction "RFP_P$6") (pintype "bidirectional"))
    )
    (net (code "26") (name "Net-(R9-2)") (class "Default")
      (node (ref "R9") (pin "P$2") (pinfunction "2_P$2") (pintype "passive"))
      (node (ref "U1") (pin "P$44") (pinfunction "ANT_A_P$44") (pintype "bidirectional"))
    )
    (net (code "27") (name "Net-(U1-EXTAL32)") (class "Default")
      (node (ref "C3") (pin "1") (pinfunction "1_1") (pintype "passive"))
      (node (ref "U1") (pin "P$31") (pinfunction "EXTAL32_P$31") (pintype "bidirectional"))
      (node (ref "X1") (pin "P$1") (pinfunction "1_P$1") (pintype "passive"))
    )
    (net (code "28") (name "Net-(U1-EXTAL_32M)") (class "Default")
      (node (ref "C2") (pin "1") (pinfunction "1_1") (pintype "passive"))
      (node (ref "U1") (pin "P$1") (pinfunction "EXTAL_32M_P$1") (pintype "bidirectional"))
      (node (ref "X2") (pin "P$1") (pinfunction "P$1_P$1") (pintype "passive"))
    )
    (net (code "29") (name "Net-(U1-GPIO1)") (class "Default")
      (node (ref "J1") (pin "P$30") (pinfunction "P$30_P$30") (pintype "bidirectional"))
      (node (ref "U1") (pin "P$2") (pinfunction "GPIO1_P$2") (pintype "bidirectional"))
    )
    (net (code "30") (name "Net-(U1-PTA0{slash}JTAG_TCLK{slash}SWD_CLK{slash}EZP_CLK{slash}~{UART0_CTS{slash}}UART0_COL{slash}FTM0_CH5)") (class "Default")
      (node (ref "J1") (pin "P$8") (pinfunction "P$8_P$8") (pintype "bidirectional"))
      (node (ref "TP4") (pin "TP") (pinfunction "TP_TP") (pintype "input"))
      (node (ref "U1") (pin "P$33") (pinfunction "PTA0/JTAG_TCLK/SWD_CLK/EZP_CLK/~{UART0_CTS/}UART0_COL/FTM0_CH5_P$33") (pintype "bidirectional"))
    )
    (net (code "31") (name "Net-(U1-PTA1{slash}JTAG_TDI{slash}EZP_DI{slash}UART0{slash}RX{slash}FTM0_CH6)") (class "Default")
      (node (ref "J1") (pin "P$10") (pinfunction "P$10_P$10") (pintype "bidirectional"))
      (node (ref "TP3") (pin "TP") (pinfunction "TP_TP") (pintype "input"))
      (node (ref "U1") (pin "P$34") (pinfunction "PTA1/JTAG_TDI/EZP_DI/UART0/RX/FTM0_CH6_P$34") (pintype "bidirectional"))
    )
    (net (code "32") (name "Net-(U1-PTA2{slash}JTAG_TDO{slash}TRACE?SWO{slash}EZP_DO{slash}UART0_TX{slash}FTM0_CH7)") (class "Default")
      (node (ref "J1") (pin "P$12") (pinfunction "P$12_P$12") (pintype "bidirectional"))
      (node (ref "TP2") (pin "TP") (pinfunction "TP_TP") (pintype "input"))
      (node (ref "U1") (pin "P$35") (pinfunction "PTA2/JTAG_TDO/TRACE?SWO/EZP_DO/UART0_TX/FTM0_CH7_P$35") (pintype "bidirectional"))
    )
    (net (code "33") (name "Net-(U1-PTA3{slash}JTAG_TMS{slash}SWD_DIO{slash}UART0_RTS{slash}FTM0_CH0)") (class "Default")
      (node (ref "J1") (pin "P$14") (pinfunction "P$14_P$14") (pintype "bidirectional"))
      (node (ref "TP1") (pin "TP") (pinfunction "TP_TP") (pintype "input"))
      (node (ref "U1") (pin "P$36") (pinfunction "PTA3/JTAG_TMS/SWD_DIO/UART0_RTS/FTM0_CH0_P$36") (pintype "bidirectional"))
    )
    (net (code "34") (name "Net-(U1-PTA4{slash}LLWU_P3{slash}~{NMI}{slash}~{EZP_CS}{slash}FTM0_CH1)") (class "Default")
      (node (ref "J1") (pin "P$16") (pinfunction "P$16_P$16") (pintype "bidirectional"))
      (node (ref "U1") (pin "P$37") (pinfunction "PTA4/LLWU_P3/~{NMI}/~{EZP_CS}/FTM0_CH1_P$37") (pintype "bidirectional"))
    )
    (net (code "35") (name "Net-(U1-PTA18{slash}EXTAL0{slash}FTM0_FTL2_FTM_CLKIN0)") (class "Default")
      (node (ref "J1") (pin "P$18") (pinfunction "P$18_P$18") (pintype "bidirectional"))
      (node (ref "U1") (pin "P$39") (pinfunction "PTA18/EXTAL0/FTM0_FTL2_FTM_CLKIN0_P$39") (pintype "bidirectional"))
    )
    (net (code "36") (name "Net-(U1-PTA19{slash}XTAL0{slash}FTM1_FLT0{slash}FTM_CLKIN1{slash}LPTMR0_ALT1)") (class "Default")
      (node (ref "J1") (pin "P$20") (pinfunction "P$20_P$20") (pintype "bidirectional"))
      (node (ref "U1") (pin "P$40") (pinfunction "PTA19/XTAL0/FTM1_FLT0/FTM_CLKIN1/LPTMR0_ALT1_P$40") (pintype "bidirectional"))
    )
    (net (code "37") (name "Net-(U1-PTC4{slash}LLWU_P8{slash}SPI0_PCS0{slash}UART1_TX{slash}FTM0_CH3{slash}CMP1_OUT)") (class "Default")
      (node (ref "J1") (pin "P$22") (pinfunction "P$22_P$22") (pintype "bidirectional"))
      (node (ref "TP13") (pin "TP") (pinfunction "TP_TP") (pintype "input"))
      (node (ref "U1") (pin "P$4") (pinfunction "PTC4/LLWU_P8/SPI0_PCS0/UART1_TX/FTM0_CH3/CMP1_OUT_P$4") (pintype "bidirectional"))
    )
    (net (code "38") (name "Net-(U1-PTD1{slash}ADC0_SE5B{slash}SPI0_SCK{slash}~{UART2_CTS})") (class "Default")
      (node (ref "J1") (pin "P$5") (pinfunction "P$5_P$5") (pintype "bidirectional"))
      (node (ref "U1") (pin "P$8") (pinfunction "PTD1/ADC0_SE5B/SPI0_SCK/~{UART2_CTS}_P$8") (pintype "bidirectional"))
    )
    (net (code "39") (name "Net-(U1-PTD2{slash}LLWU_P13{slash}SPI0_SOUT{slash}UART2_RX{slash}I2C0_SDA{slash}GPIO4_BSM_DATA)") (class "Default")
      (node (ref "J1") (pin "P$7") (pinfunction "P$7_P$7") (pintype "bidirectional"))
      (node (ref "U1") (pin "P$9") (pinfunction "PTD2/LLWU_P13/SPI0_SOUT/UART2_RX/I2C0_SDA/GPIO4_BSM_DATA_P$9") (pintype "bidirectional"))
    )
    (net (code "40") (name "Net-(U1-PTD3{slash}SPI0_SIN{slash}UART2_TX{slash}I2C0_SCL{slash}GPIO5_BSM_CLK)") (class "Default")
      (node (ref "J1") (pin "P$9") (pinfunction "P$9_P$9") (pintype "bidirectional"))
      (node (ref "U1") (pin "P$10") (pinfunction "PTD3/SPI0_SIN/UART2_TX/I2C0_SCL/GPIO5_BSM_CLK_P$10") (pintype "bidirectional"))
    )
    (net (code "41") (name "Net-(U1-PTD4{slash}LLWU_P14{slash}MADC0_SE21{slash}SPI0_PCS1{slash}~{UART0_RTS}{slash}FTM0_CH4{slash}EWM_IN{slash}GPIO_BSM_FRAME)") (class "Default")
      (node (ref "J1") (pin "P$11") (pinfunction "P$11_P$11") (pintype "bidirectional"))
      (node (ref "TP9") (pin "TP") (pinfunction "TP_TP") (pintype "input"))
      (node (ref "U1") (pin "P$11") (pinfunction "PTD4/LLWU_P14/MADC0_SE21/SPI0_PCS1/~{UART0_RTS}/FTM0_CH4/EWM_IN/GPIO_BSM_FRAME_P$11") (pintype "bidirectional"))
    )
    (net (code "42") (name "Net-(U1-PTD6{slash}LLWU_P15{slash}ADC0_SE7B{slash}SPI0_PCS3{slash}UART0_RX{slash}FTM0_CH6{slash}FTM0_FLT0)") (class "Default")
      (node (ref "J1") (pin "P$15") (pinfunction "P$15_P$15") (pintype "bidirectional"))
      (node (ref "TP11") (pin "TP") (pinfunction "TP_TP") (pintype "input"))
      (node (ref "U1") (pin "P$13") (pinfunction "PTD6/LLWU_P15/ADC0_SE7B/SPI0_PCS3/UART0_RX/FTM0_CH6/FTM0_FLT0_P$13") (pintype "bidirectional"))
    )
    (net (code "43") (name "Net-(U1-PTD7{slash}MADC0_SE22{slash}CMT_IRO{slash}UART0_TX{slash}FTM0_CH7{slash}FTM0_FLT1)") (class "Default")
      (node (ref "J1") (pin "P$17") (pinfunction "P$17_P$17") (pintype "bidirectional"))
      (node (ref "TP12") (pin "TP") (pinfunction "TP_TP") (pintype "input"))
      (node (ref "U1") (pin "P$14") (pinfunction "PTD7/MADC0_SE22/CMT_IRO/UART0_TX/FTM0_CH7/FTM0_FLT1_P$14") (pintype "bidirectional"))
    )
    (net (code "44") (name "Net-(U1-PTE0{slash}MADC0_SE10{slash}SPI1_PCS1{slash}UART1_TX{slash}MTRACE_CLKOUT{slash}I2C1_SDA{slash}RTC_CLKOUT)") (class "Default")
      (node (ref "J1") (pin "P$19") (pinfunction "P$19_P$19") (pintype "bidirectional"))
      (node (ref "TP15") (pin "TP") (pinfunction "TP_TP") (pintype "input"))
      (node (ref "U1") (pin "P$15") (pinfunction "PTE0/MADC0_SE10/SPI1_PCS1/UART1_TX/MTRACE_CLKOUT/I2C1_SDA/RTC_CLKOUT_P$15") (pintype "bidirectional"))
    )
    (net (code "45") (name "Net-(U1-PTE1{slash}LLWU_P0{slash}MADC0_SE11{slash}SPI1_SOUT{slash}UART1_RX{slash}MTRACE_D3{slash}I2C1_SCL{slash}SPI1_SIN)") (class "Default")
      (node (ref "J1") (pin "P$21") (pinfunction "P$21_P$21") (pintype "bidirectional"))
      (node (ref "TP16") (pin "TP") (pinfunction "TP_TP") (pintype "input"))
      (node (ref "U1") (pin "P$16") (pinfunction "PTE1/LLWU_P0/MADC0_SE11/SPI1_SOUT/UART1_RX/MTRACE_D3/I2C1_SCL/SPI1_SIN_P$16") (pintype "bidirectional"))
    )
    (net (code "46") (name "Net-(U1-PTE2{slash}LLWU_P1{slash}MADC0_DP1{slash}SPI1_SCK{slash}~{UART1_CTS}{slash}MTRACE_D2)") (class "Default")
      (node (ref "J1") (pin "P$23") (pinfunction "P$23_P$23") (pintype "bidirectional"))
      (node (ref "TP17") (pin "TP") (pinfunction "TP_TP") (pintype "input"))
      (node (ref "U1") (pin "P$17") (pinfunction "PTE2/LLWU_P1/MADC0_DP1/SPI1_SCK/~{UART1_CTS}/MTRACE_D2_P$17") (pintype "bidirectional"))
    )
    (net (code "47") (name "Net-(U1-PTE3{slash}MADC0_DM1{slash}SPI1_SIN{slash}~{UART1_RTS}{slash}MTRACE_D1{slash}SPI1_SOUT)") (class "Default")
      (node (ref "J1") (pin "P$25") (pinfunction "P$25_P$25") (pintype "bidirectional"))
      (node (ref "TP18") (pin "TP") (pinfunction "TP_TP") (pintype "input"))
      (node (ref "U1") (pin "P$18") (pinfunction "PTE3/MADC0_DM1/SPI1_SIN/~{UART1_RTS}/MTRACE_D1/SPI1_SOUT_P$18") (pintype "bidirectional"))
    )
    (net (code "48") (name "Net-(U1-PTE4{slash}LLWU_P2{slash}SPI1_PCS0{slash}MTRACE_D0)") (class "Default")
      (node (ref "J1") (pin "P$27") (pinfunction "P$27_P$27") (pintype "bidirectional"))
      (node (ref "U1") (pin "P$19") (pinfunction "PTE4/LLWU_P2/SPI1_PCS0/MTRACE_D0_P$19") (pintype "bidirectional"))
    )
    (net (code "49") (name "Net-(U1-PTE16{slash}ADC0_SE4A{slash}SPI0_PCS0{slash}UART2_TX{slash}FTM_CLKIN0{slash}FTM0_FLT3)") (class "Default")
      (node (ref "J1") (pin "P$29") (pinfunction "P$29_P$29") (pintype "bidirectional"))
      (node (ref "U1") (pin "P$21") (pinfunction "PTE16/ADC0_SE4A/SPI0_PCS0/UART2_TX/FTM_CLKIN0/FTM0_FLT3_P$21") (pintype "bidirectional"))
    )
    (net (code "50") (name "Net-(U1-PTE17{slash}ADC0_SE5A{slash}SPI0_SCK{slash}UART2_RX{slash}FTM_CLKIN1{slash}LPTMR0_ALT3)") (class "Default")
      (node (ref "J1") (pin "P$31") (pinfunction "P$31_P$31") (pintype "bidirectional"))
      (node (ref "U1") (pin "P$22") (pinfunction "PTE17/ADC0_SE5A/SPI0_SCK/UART2_RX/FTM_CLKIN1/LPTMR0_ALT3_P$22") (pintype "bidirectional"))
    )
    (net (code "51") (name "Net-(U1-PTE18{slash}ADC0_SE6A{slash}SPI0_SOUT{slash}~{UART2_CTS}{slash}I2C0_SDA)") (class "Default")
      (node (ref "J1") (pin "P$33") (pinfunction "P$33_P$33") (pintype "bidirectional"))
      (node (ref "U1") (pin "P$23") (pinfunction "PTE18/ADC0_SE6A/SPI0_SOUT/~{UART2_CTS}/I2C0_SDA_P$23") (pintype "bidirectional"))
    )
    (net (code "52") (name "Net-(U1-PTE19{slash}ADC0_SE7A{slash}SPI0_SIN{slash}~{UART2_RTS}{slash}I2C0_SCL)") (class "Default")
      (node (ref "J1") (pin "P$35") (pinfunction "P$35_P$35") (pintype "bidirectional"))
      (node (ref "U1") (pin "P$24") (pinfunction "PTE19/ADC0_SE7A/SPI0_SIN/~{UART2_RTS}/I2C0_SCL_P$24") (pintype "bidirectional"))
    )
    (net (code "53") (name "Net-(U1-TAMPER0{slash}~{RTC_WAKEUP})") (class "Default")
      (node (ref "R1") (pin "2") (pinfunction "2_2") (pintype "passive"))
      (node (ref "U1") (pin "P$29") (pinfunction "TAMPER0/~{RTC_WAKEUP}_P$29") (pintype "bidirectional"))
    )
    (net (code "54") (name "Net-(U1-XTAL32)") (class "Default")
      (node (ref "C4") (pin "1") (pinfunction "1_1") (pintype "passive"))
      (node (ref "U1") (pin "P$30") (pinfunction "XTAL32_P$30") (pintype "bidirectional"))
      (node (ref "X1") (pin "P$2") (pinfunction "2_P$2") (pintype "passive"))
    )
    (net (code "55") (name "Net-(U1-XTAL_32M)") (class "Default")
      (node (ref "C1") (pin "1") (pinfunction "1_1") (pintype "passive"))
      (node (ref "U1") (pin "P$56") (pinfunction "XTAL_32M_P$56") (pintype "bidirectional"))
      (node (ref "X2") (pin "P$3") (pinfunction "P$3_P$3") (pintype "passive"))
    )
    (net (code "56") (name "Net-(U1-~{RESET})") (class "Default")
      (node (ref "J1") (pin "P$6") (pinfunction "P$6_P$6") (pintype "bidirectional"))
      (node (ref "R10") (pin "1") (pinfunction "1_1") (pintype "passive"))
      (node (ref "TP5") (pin "TP") (pinfunction "TP_TP") (pintype "input"))
      (node (ref "U1") (pin "P$41") (pinfunction "~{RESET}_P$41") (pintype "bidirectional"))
    )
    (net (code "57") (name "unconnected-(J1-PadP$34)") (class "Default")
      (node (ref "J1") (pin "P$34") (pinfunction "P$34_P$34") (pintype "bidirectional"))
    )
    (net (code "58") (name "unconnected-(J1-PadP$36)") (class "Default")
      (node (ref "J1") (pin "P$36") (pinfunction "P$36_P$36") (pintype "bidirectional"))
    )
    (net (code "59") (name "unconnected-(J1-PadP$41)") (class "Default")
      (node (ref "J1") (pin "P$41") (pinfunction "P$41_P$41") (pintype "bidirectional"))
    )
    (net (code "60") (name "unconnected-(J1-PadP$42)") (class "Default")
      (node (ref "J1") (pin "P$42") (pinfunction "P$42_P$42") (pintype "bidirectional"))
    )
    (net (code "61") (name "unconnected-(U1-ANT_B-PadP$45)") (class "Default")
      (node (ref "U1") (pin "P$45") (pinfunction "ANT_B_P$45") (pintype "bidirectional"))
    )
    (net (code "62") (name "unconnected-(U1-NC_57-PadP$57)") (class "Default")
      (node (ref "U1") (pin "P$57") (pinfunction "NC_57_P$57") (pintype "bidirectional"))
    )
    (net (code "63") (name "unconnected-(U1-NC_58-PadP$58)") (class "Default")
      (node (ref "U1") (pin "P$58") (pinfunction "NC_58_P$58") (pintype "bidirectional"))
    )
    (net (code "64") (name "unconnected-(U1-NC_59-PadP$59)") (class "Default")
      (node (ref "U1") (pin "P$59") (pinfunction "NC_59_P$59") (pintype "bidirectional"))
    )
    (net (code "65") (name "unconnected-(U1-NC_60-PadP$60)") (class "Default")
      (node (ref "U1") (pin "P$60") (pinfunction "NC_60_P$60") (pintype "bidirectional"))
    )
    (net (code "66") (name "unconnected-(U1-NC_61-PadP$61)") (class "Default")
      (node (ref "U1") (pin "P$61") (pinfunction "NC_61_P$61") (pintype "bidirectional"))
    )
    (net (code "67") (name "unconnected-(U1-NC_62-PadP$62)") (class "Default")
      (node (ref "U1") (pin "P$62") (pinfunction "NC_62_P$62") (pintype "bidirectional"))
    )
    (net (code "68") (name "unconnected-(U1-RX_SWITCH-PadP$46)") (class "Default")
      (node (ref "U1") (pin "P$46") (pinfunction "RX_SWITCH_P$46") (pintype "bidirectional"))
    )
    (net (code "69") (name "unconnected-(U3-CT-PadP$4)") (class "Default")
      (node (ref "U3") (pin "P$4") (pinfunction "CT_P$4") (pintype "bidirectional"))
    )
    (net (code "70") (name "unconnected-(U3-N{slash}C-PadP$11)") (class "Default")
      (node (ref "U3") (pin "P$11") (pinfunction "N/C_P$11") (pintype "bidirectional"))
    )
    (net (code "71") (name "unconnected-(U3-N{slash}C1-PadP$21)") (class "Default")
      (node (ref "U3") (pin "P$21") (pinfunction "N/C1_P$21") (pintype "bidirectional"))
    )
    (net (code "72") (name "unconnected-(U3-PadP$25)") (class "Default")
      (node (ref "U3") (pin "P$25") (pinfunction "P$25_P$25") (pintype "bidirectional"))
    )
  )
)
